# amplifier_board.net
KiCad netlist of a schematic drawn in EAGLE
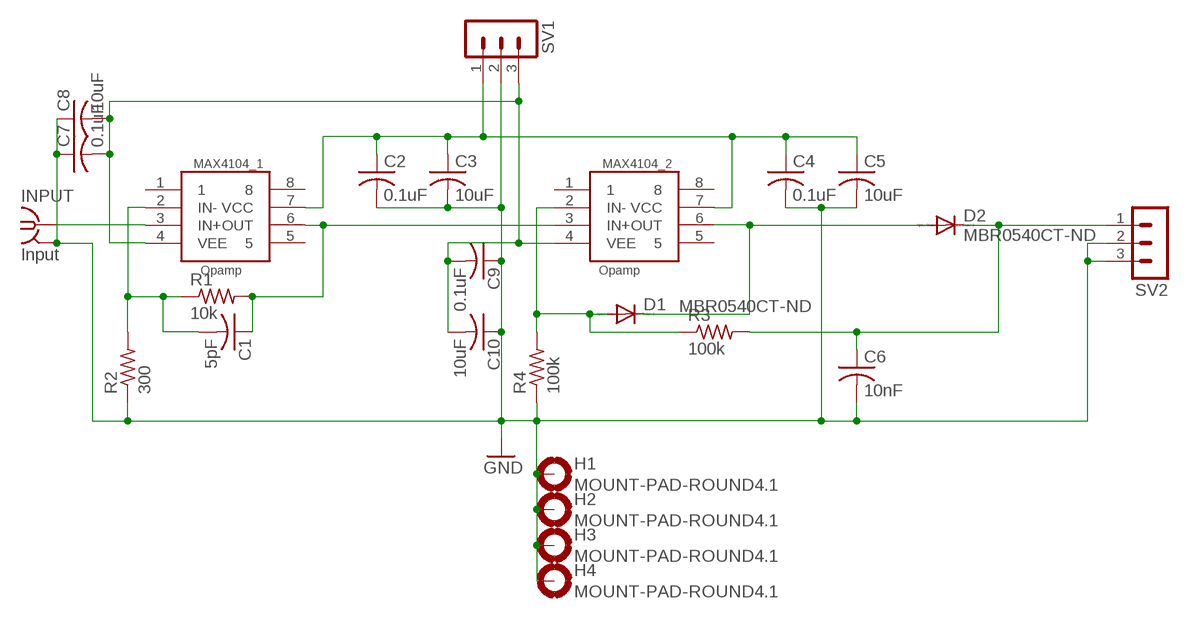
[diagram p0: schematic, sheet 1]

(export (version "E")
  (design (tool "Eeschema 10.0.6"))
  (components
    (comp (ref "C1")
      (value "5pF")
      (footprint "eagle-import:C0603")
      (libsource (lib "eagle-import") (part "C-USC0603"))
    )
    (comp (ref "C2")
      (value "0.1uF")
      (footprint "eagle-import:C0603")
      (libsource (lib "eagle-import") (part "C-USC0603"))
    )
    (comp (ref "C3")
      (value "10uF")
      (footprint "eagle-import:C0603")
      (libsource (lib "eagle-import") (part "C-USC0603"))
    )
    (comp (ref "C4")
      (value "0.1uF")
      (footprint "eagle-import:C0603")
      (libsource (lib "eagle-import") (part "C-USC0603"))
    )
    (comp (ref "C5")
      (value "10uF")
      (footprint "eagle-import:C0603")
      (libsource (lib "eagle-import") (part "C-USC0603"))
    )
    (comp (ref "C6")
      (value "10nF")
      (footprint "eagle-import:C0603")
      (libsource (lib "eagle-import") (part "C-USC0603"))
    )
    (comp (ref "C7")
      (value "0.1uF")
      (footprint "eagle-import:C0603")
      (libsource (lib "eagle-import") (part "C-USC0603"))
    )
    (comp (ref "C8")
      (value "10uF")
      (footprint "eagle-import:C0603")
      (libsource (lib "eagle-import") (part "C-USC0603"))
    )
    (comp (ref "C9")
      (value "0.1uF")
      (footprint "eagle-import:C0603")
      (libsource (lib "eagle-import") (part "C-USC0603"))
    )
    (comp (ref "C10")
      (value "10uF")
      (footprint "eagle-import:C0603")
      (libsource (lib "eagle-import") (part "C-USC0603"))
    )
    (comp (ref "D1")
      (value "MBR0540CT-ND")
      (footprint "eagle-import:SOD-123_MINI-SMA")
      (fields (field (name "SPICEMODEL") "DMBR0540") (field (name "SPICEPREFIX") "D"))
      (libsource (lib "eagle-import") (part "CGRM400-G1"))
    )
    (comp (ref "D2")
      (value "MBR0540CT-ND")
      (footprint "eagle-import:SOD-123_MINI-SMA")
      (fields (field (name "SPICEMODEL") "DMBR0540") (field (name "SPICEPREFIX") "D"))
      (libsource (lib "eagle-import") (part "CGRM400-G1"))
    )
    (comp (ref "H1")
      (value "MOUNT-PAD-ROUND4.1")
      (footprint "eagle-import:4,1-PAD")
      (libsource (lib "eagle-import") (part "MOUNT-PAD-ROUND4.1"))
    )
    (comp (ref "H2")
      (value "MOUNT-PAD-ROUND4.1")
      (footprint "eagle-import:4,1-PAD")
      (libsource (lib "eagle-import") (part "MOUNT-PAD-ROUND4.1"))
    )
    (comp (ref "H3")
      (value "MOUNT-PAD-ROUND4.1")
      (footprint "eagle-import:4,1-PAD")
      (libsource (lib "eagle-import") (part "MOUNT-PAD-ROUND4.1"))
    )
    (comp (ref "H4")
      (value "MOUNT-PAD-ROUND4.1")
      (footprint "eagle-import:4,1-PAD")
      (libsource (lib "eagle-import") (part "MOUNT-PAD-ROUND4.1"))
    )
    (comp (ref "INPUT")
      (value "Input")
      (footprint "eagle-import:SMA-EDGE")
      (fields (field (name "SPICEPREFIX") "V"))
      (libsource (lib "eagle-import") (part "SMA-EDGE"))
    )
    (comp (ref "MAX4104_1")
      (value "Opamp")
      (footprint "eagle-import:SO8")
      (fields (field (name "SPICEMODEL") "MAX4104") (field (name "SPICEPREFIX") "X"))
      (libsource (lib "eagle-import") (part "MAX4104"))
    )
    (comp (ref "MAX4104_2")
      (value "Opamp")
      (footprint "eagle-import:SO8")
      (fields (field (name "SPICEMODEL") "MAX4104") (field (name "SPICEPREFIX") "X"))
      (libsource (lib "eagle-import") (part "MAX4104"))
    )
    (comp (ref "R1")
      (value "10k")
      (footprint "eagle-import:R0603")
      (libsource (lib "eagle-import") (part "R-US_R0603"))
    )
    (comp (ref "R2")
      (value "300")
      (footprint "eagle-import:R0603")
      (libsource (lib "eagle-import") (part "R-US_R0603"))
    )
    (comp (ref "R3")
      (value "100k")
      (footprint "eagle-import:R0603")
      (libsource (lib "eagle-import") (part "R-US_R0603"))
    )
    (comp (ref "R4")
      (value "100k")
      (footprint "eagle-import:R0603")
      (libsource (lib "eagle-import") (part "R-US_R0603"))
    )
    (comp (ref "SV1")
      (value "MA03-1")
      (footprint "eagle-import:MA03-1")
      (libsource (lib "eagle-import") (part "MA03-1"))
    )
    (comp (ref "SV2")
      (value "MA03-1")
      (footprint "eagle-import:MA03-1")
      (libsource (lib "eagle-import") (part "MA03-1"))
    )
  )
  (nets
    (net (code "1") (name "/AMP") (class "Default")
      (node (ref "C1") (pin "1") (pinfunction "1_1") (pintype "passive"))
      (node (ref "MAX4104_1") (pin "6") (pinfunction "OUT_6") (pintype "output"))
      (node (ref "MAX4104_2") (pin "3") (pinfunction "IN+_3") (pintype "input"))
      (node (ref "R1") (pin "2") (pinfunction "2_2") (pintype "passive"))
    )
    (net (code "2") (name "/DIG_READOUT") (class "Default")
      (node (ref "C6") (pin "1") (pinfunction "1_1") (pintype "passive"))
      (node (ref "D2") (pin "C") (pinfunction "C_C") (pintype "passive"))
      (node (ref "R3") (pin "2") (pinfunction "2_2") (pintype "passive"))
      (node (ref "SV2") (pin "1") (pinfunction "1_1") (pintype "passive"))
    )
    (net (code "3") (name "/IN") (class "Default")
      (node (ref "INPUT") (pin "G@0") (pinfunction "1_G@0") (pintype "passive"))
      (node (ref "MAX4104_1") (pin "3") (pinfunction "IN+_3") (pintype "input"))
    )
    (net (code "4") (name "/IN-_1") (class "Default")
      (node (ref "C1") (pin "2") (pinfunction "2_2") (pintype "passive"))
      (node (ref "MAX4104_1") (pin "2") (pinfunction "IN-_2") (pintype "input"))
      (node (ref "R1") (pin "1") (pinfunction "1_1") (pintype "passive"))
      (node (ref "R2") (pin "2") (pinfunction "2_2") (pintype "passive"))
    )
    (net (code "5") (name "/IN-_2") (class "Default")
      (node (ref "D1") (pin "A") (pinfunction "A_A") (pintype "passive"))
      (node (ref "MAX4104_2") (pin "2") (pinfunction "IN-_2") (pintype "input"))
      (node (ref "R3") (pin "1") (pinfunction "1_1") (pintype "passive"))
      (node (ref "R4") (pin "2") (pinfunction "2_2") (pintype "passive"))
    )
    (net (code "6") (name "/OUT_2") (class "Default")
      (node (ref "D1") (pin "C") (pinfunction "C_C") (pintype "passive"))
      (node (ref "D2") (pin "A") (pinfunction "A_A") (pintype "passive"))
      (node (ref "MAX4104_2") (pin "6") (pinfunction "OUT_6") (pintype "output"))
    )
    (net (code "7") (name "/VCC") (class "Default")
      (node (ref "C2") (pin "1") (pinfunction "1_1") (pintype "passive"))
      (node (ref "C3") (pin "1") (pinfunction "1_1") (pintype "passive"))
      (node (ref "C4") (pin "1") (pinfunction "1_1") (pintype "passive"))
      (node (ref "C5") (pin "1") (pinfunction "1_1") (pintype "passive"))
      (node (ref "MAX4104_1") (pin "7") (pinfunction "VCC_7") (pintype "power_in"))
      (node (ref "MAX4104_2") (pin "7") (pinfunction "VCC_7") (pintype "power_in"))
      (node (ref "SV1") (pin "1") (pinfunction "1_1") (pintype "passive"))
    )
    (net (code "8") (name "GND") (class "Default")
      (node (ref "C10") (pin "1") (pinfunction "1_1") (pintype "passive"))
      (node (ref "C2") (pin "2") (pinfunction "2_2") (pintype "passive"))
      (node (ref "C3") (pin "2") (pinfunction "2_2") (pintype "passive"))
      (node (ref "C4") (pin "2") (pinfunction "2_2") (pintype "passive"))
      (node (ref "C5") (pin "2") (pinfunction "2_2") (pintype "passive"))
      (node (ref "C6") (pin "2") (pinfunction "2_2") (pintype "passive"))
      (node (ref "C7") (pin "1") (pinfunction "1_1") (pintype "passive"))
      (node (ref "C8") (pin "1") (pinfunction "1_1") (pintype "passive"))
      (node (ref "C9") (pin "1") (pinfunction "1_1") (pintype "passive"))
      (node (ref "H1") (pin "B4,1") (pinfunction "MOUNT_B4,1") (pintype "passive"))
      (node (ref "H2") (pin "B4,1") (pinfunction "MOUNT_B4,1") (pintype "passive"))
      (node (ref "H3") (pin "B4,1") (pinfunction "MOUNT_B4,1") (pintype "passive"))
      (node (ref "H4") (pin "B4,1") (pinfunction "MOUNT_B4,1") (pintype "passive"))
      (node (ref "INPUT") (pin "G@1") (pinfunction "2_G@1") (pintype "passive"))
      (node (ref "INPUT") (pin "G@2") (pinfunction "2_G@2") (pintype "passive"))
      (node (ref "INPUT") (pin "G@3") (pinfunction "2_G@3") (pintype "passive"))
      (node (ref "INPUT") (pin "G@4") (pinfunction "2_G@4") (pintype "passive"))
      (node (ref "R2") (pin "1") (pinfunction "1_1") (pintype "passive"))
      (node (ref "R4") (pin "1") (pinfunction "1_1") (pintype "passive"))
      (node (ref "SV1") (pin "2") (pinfunction "2_2") (pintype "passive"))
      (node (ref "SV2") (pin "2") (pinfunction "2_2") (pintype "passive"))
      (node (ref "SV2") (pin "3") (pinfunction "3_3") (pintype "passive"))
    )
    (net (code "9") (name "Net-(MAX4104_1-VEE)") (class "Default")
      (node (ref "C10") (pin "2") (pinfunction "2_2") (pintype "passive"))
      (node (ref "C7") (pin "2") (pinfunction "2_2") (pintype "passive"))
      (node (ref "C8") (pin "2") (pinfunction "2_2") (pintype "passive"))
      (node (ref "C9") (pin "2") (pinfunction "2_2") (pintype "passive"))
      (node (ref "MAX4104_1") (pin "4") (pinfunction "VEE_4") (pintype "power_in"))
      (node (ref "MAX4104_2") (pin "4") (pinfunction "VEE_4") (pintype "power_in"))
      (node (ref "SV1") (pin "3") (pinfunction "3_3") (pintype "passive"))
    )
    (net (code "10") (name "unconnected-(MAX4104_1-Pad1)") (class "Default")
      (node (ref "MAX4104_1") (pin "1") (pinfunction "1_1") (pintype "no_connect"))
    )
    (net (code "11") (name "unconnected-(MAX4104_1-Pad5)") (class "Default")
      (node (ref "MAX4104_1") (pin "5") (pinfunction "5_5") (pintype "no_connect"))
    )
    (net (code "12") (name "unconnected-(MAX4104_1-Pad8)") (class "Default")
      (node (ref "MAX4104_1") (pin "8") (pinfunction "8_8") (pintype "no_connect"))
    )
    (net (code "13") (name "unconnected-(MAX4104_2-Pad1)") (class "Default")
      (node (ref "MAX4104_2") (pin "1") (pinfunction "1_1") (pintype "no_connect"))
    )
    (net (code "14") (name "unconnected-(MAX4104_2-Pad5)") (class "Default")
      (node (ref "MAX4104_2") (pin "5") (pinfunction "5_5") (pintype "no_connect"))
    )
    (net (code "15") (name "unconnected-(MAX4104_2-Pad8)") (class "Default")
      (node (ref "MAX4104_2") (pin "8") (pinfunction "8_8") (pintype "no_connect"))
    )
  )
)
